# BRD1001-001-010-320_-_Clock.net
KiCad netlist of a schematic drawn in EAGLE
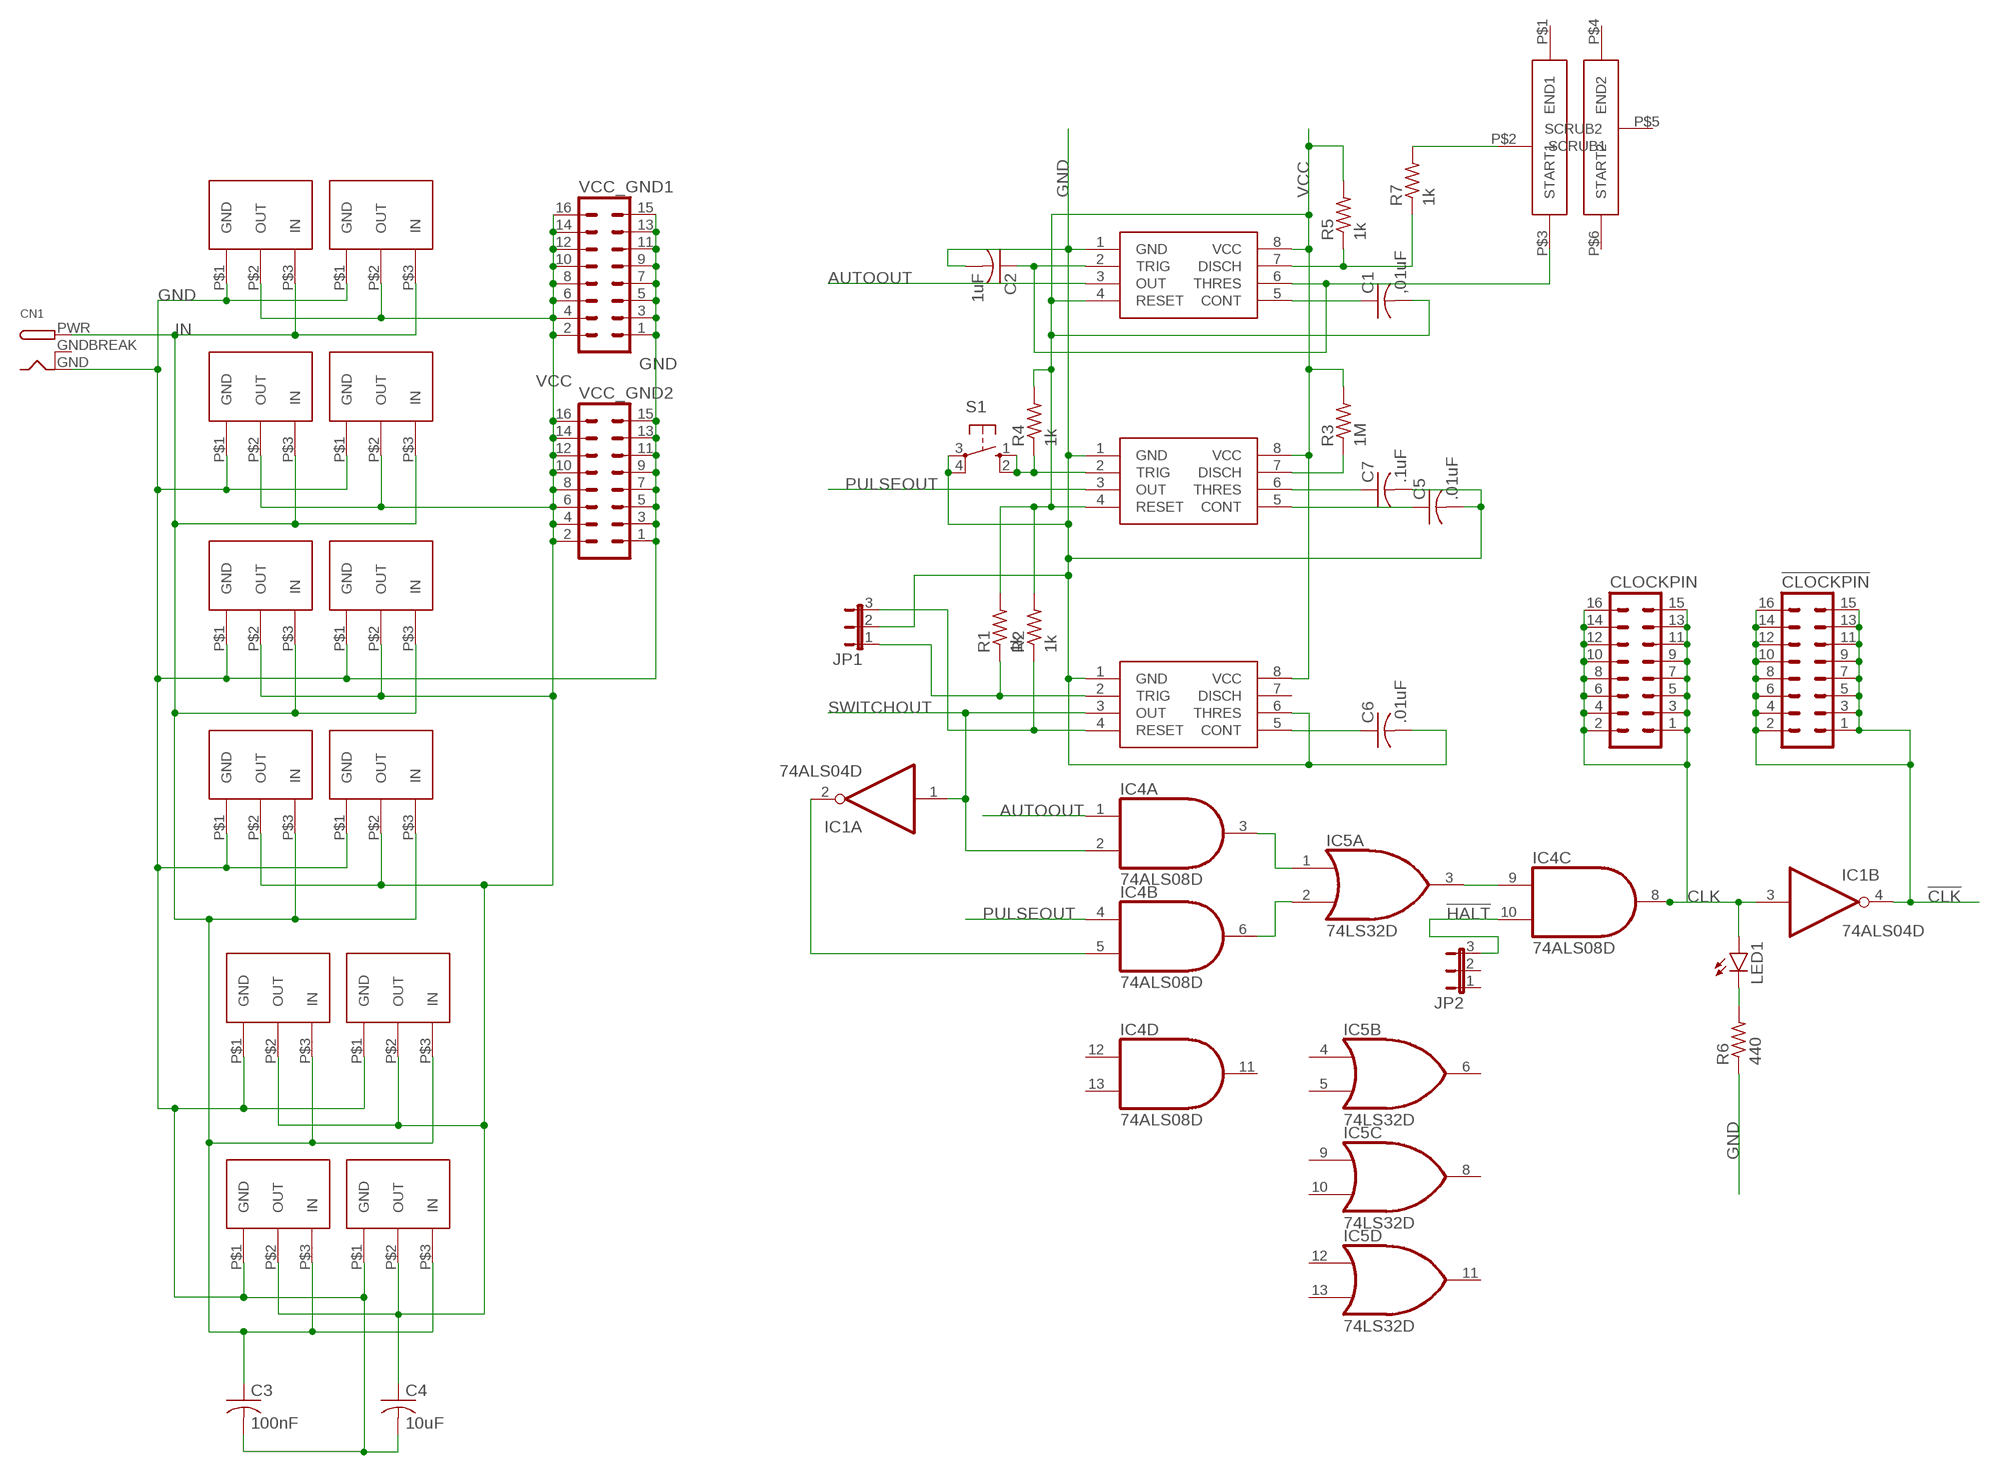
[diagram p0: schematic, sheet 1]

(export (version "E")
  (design (tool "Eeschema 10.0.6"))
  (components
    (comp (ref "!CLOCKPIN")
      (value "ML16")
      (footprint "eagle-import:ML16")
      (libsource (lib "eagle-import") (part "ML16"))
    )
    (comp (ref "AUTO")
      (value "NA555")
      (footprint "eagle-import:SO8")
      (libsource (lib "eagle-import") (part "NA555"))
    )
    (comp (ref "C1")
      (value ",01uF")
      (footprint "eagle-import:C025-024X044")
      (libsource (lib "eagle-import") (part "C-US025-024X044"))
    )
    (comp (ref "C2")
      (value "1uF")
      (footprint "eagle-import:C025-024X044")
      (libsource (lib "eagle-import") (part "C-US025-024X044"))
    )
    (comp (ref "C3")
      (value "100nF")
      (footprint "eagle-import:C025-024X044")
      (libsource (lib "eagle-import") (part "C-US025-024X044"))
    )
    (comp (ref "C4")
      (value "10uF")
      (footprint "eagle-import:C025-024X044")
      (libsource (lib "eagle-import") (part "C-US025-024X044"))
    )
    (comp (ref "C5")
      (value ".01uF")
      (footprint "eagle-import:C025-024X044")
      (libsource (lib "eagle-import") (part "C-US025-024X044"))
    )
    (comp (ref "C6")
      (value ".01uF")
      (footprint "eagle-import:C025-024X044")
      (libsource (lib "eagle-import") (part "C-US025-024X044"))
    )
    (comp (ref "C7")
      (value ".1uF")
      (footprint "eagle-import:C025-024X044")
      (libsource (lib "eagle-import") (part "C-US025-024X044"))
    )
    (comp (ref "CLOCKPIN")
      (value "ML16")
      (footprint "eagle-import:ML16")
      (libsource (lib "eagle-import") (part "ML16"))
    )
    (comp (ref "CN1")
      (value "DCBARRELPTH")
      (footprint "eagle-import:DCJACK_2MM_PTH")
      (libsource (lib "eagle-import") (part "DCBARRELPTH"))
    )
    (comp (ref "IC1")
      (value "74ALS04D")
      (footprint "eagle-import:SO14")
      (libsource (lib "eagle-import") (part "7404DALS"))
    )
    (comp (ref "IC4")
      (value "74ALS08D")
      (footprint "eagle-import:SO14")
      (libsource (lib "eagle-import") (part "7408DALS"))
    )
    (comp (ref "IC5")
      (value "74LS32D")
      (footprint "eagle-import:SO14")
      (libsource (lib "eagle-import") (part "7432DLS"))
    )
    (comp (ref "JP1")
      (value "JP2E")
      (footprint "eagle-import:JP2")
      (libsource (lib "eagle-import") (part "JP2E"))
    )
    (comp (ref "JP2")
      (value "JP2E")
      (footprint "eagle-import:JP2")
      (libsource (lib "eagle-import") (part "JP2E"))
    )
    (comp (ref "LED1")
      (value "LED5MM")
      (footprint "eagle-import:LED5MM")
      (libsource (lib "eagle-import") (part "LED5MM"))
    )
    (comp (ref "PULSE")
      (value "NA555")
      (footprint "eagle-import:SO8")
      (libsource (lib "eagle-import") (part "NA555"))
    )
    (comp (ref "R1")
      (value "1k")
      (footprint "eagle-import:0204V")
      (libsource (lib "eagle-import") (part "R-US_0204/2V"))
    )
    (comp (ref "R2")
      (value "1k")
      (footprint "eagle-import:0204V")
      (libsource (lib "eagle-import") (part "R-US_0204/2V"))
    )
    (comp (ref "R3")
      (value "1M")
      (footprint "eagle-import:0204V")
      (libsource (lib "eagle-import") (part "R-US_0204/2V"))
    )
    (comp (ref "R4")
      (value "1k")
      (footprint "eagle-import:0204V")
      (libsource (lib "eagle-import") (part "R-US_0204/2V"))
    )
    (comp (ref "R5")
      (value "1k")
      (footprint "eagle-import:0204V")
      (libsource (lib "eagle-import") (part "R-US_0204/2V"))
    )
    (comp (ref "R6")
      (value "440")
      (footprint "eagle-import:0204V")
      (libsource (lib "eagle-import") (part "R-US_0204/2V"))
    )
    (comp (ref "R7")
      (value "1k")
      (footprint "eagle-import:0204V")
      (libsource (lib "eagle-import") (part "R-US_0204/2V"))
    )
    (comp (ref "S1")
      (value "40-XX")
      (footprint "eagle-import:B3F-40XX")
      (fields (field (name "MF") "OMRON COMPONENTS USA") (field (name "MPN") "B3F-4000"))
      (libsource (lib "eagle-import") (part "40-XX"))
    )
    (comp (ref "SWITCH")
      (value "NA555")
      (footprint "eagle-import:SO8")
      (libsource (lib "eagle-import") (part "NA555"))
    )
    (comp (ref "U$1")
      (value "3310H-001-105L")
      (footprint "eagle-import:3310H-001-105L")
      (libsource (lib "eagle-import") (part "3310H-001-105L"))
    )
    (comp (ref "U$2")
      (value "LD1117S33TR")
      (footprint "eagle-import:AZ1117E")
      (libsource (lib "eagle-import") (part "LD1117S33TR"))
    )
    (comp (ref "U$3")
      (value "LD1117S33TR")
      (footprint "eagle-import:AZ1117E")
      (libsource (lib "eagle-import") (part "LD1117S33TR"))
    )
    (comp (ref "U$4")
      (value "LD1117S33TR")
      (footprint "eagle-import:AZ1117E")
      (libsource (lib "eagle-import") (part "LD1117S33TR"))
    )
    (comp (ref "U$5")
      (value "LD1117S33TR")
      (footprint "eagle-import:AZ1117E")
      (libsource (lib "eagle-import") (part "LD1117S33TR"))
    )
    (comp (ref "U$6")
      (value "LD1117S33TR")
      (footprint "eagle-import:AZ1117E")
      (libsource (lib "eagle-import") (part "LD1117S33TR"))
    )
    (comp (ref "U$7")
      (value "LD1117S33TR")
      (footprint "eagle-import:AZ1117E")
      (libsource (lib "eagle-import") (part "LD1117S33TR"))
    )
    (comp (ref "U$8")
      (value "LD1117S33TR")
      (footprint "eagle-import:AZ1117E")
      (libsource (lib "eagle-import") (part "LD1117S33TR"))
    )
    (comp (ref "U$9")
      (value "LD1117S33TR")
      (footprint "eagle-import:AZ1117E")
      (libsource (lib "eagle-import") (part "LD1117S33TR"))
    )
    (comp (ref "U$10")
      (value "LD1117S33TR")
      (footprint "eagle-import:AZ1117E")
      (libsource (lib "eagle-import") (part "LD1117S33TR"))
    )
    (comp (ref "U$11")
      (value "LD1117S33TR")
      (footprint "eagle-import:AZ1117E")
      (libsource (lib "eagle-import") (part "LD1117S33TR"))
    )
    (comp (ref "U$12")
      (value "LD1117S33TR")
      (footprint "eagle-import:AZ1117E")
      (libsource (lib "eagle-import") (part "LD1117S33TR"))
    )
    (comp (ref "U$13")
      (value "LD1117S33TR")
      (footprint "eagle-import:AZ1117E")
      (libsource (lib "eagle-import") (part "LD1117S33TR"))
    )
    (comp (ref "VCC_GND1")
      (value "ML16")
      (footprint "eagle-import:ML16")
      (libsource (lib "eagle-import") (part "ML16"))
    )
    (comp (ref "VCC_GND2")
      (value "ML16")
      (footprint "eagle-import:ML16")
      (libsource (lib "eagle-import") (part "ML16"))
    )
  )
  (nets
    (net (code "1") (name "/AUTOOUT") (class "Default")
      (node (ref "AUTO") (pin "3") (pinfunction "OUT_3") (pintype "bidirectional"))
      (node (ref "IC4") (pin "1") (pinfunction "I0_1") (pintype "input"))
    )
    (net (code "2") (name "/CLK") (class "Default")
      (node (ref "CLOCKPIN") (pin "1") (pinfunction "1_1") (pintype "passive"))
      (node (ref "CLOCKPIN") (pin "10") (pinfunction "10_10") (pintype "passive"))
      (node (ref "CLOCKPIN") (pin "11") (pinfunction "11_11") (pintype "passive"))
      (node (ref "CLOCKPIN") (pin "12") (pinfunction "12_12") (pintype "passive"))
      (node (ref "CLOCKPIN") (pin "13") (pinfunction "13_13") (pintype "passive"))
      (node (ref "CLOCKPIN") (pin "14") (pinfunction "14_14") (pintype "passive"))
      (node (ref "CLOCKPIN") (pin "15") (pinfunction "15_15") (pintype "passive"))
      (node (ref "CLOCKPIN") (pin "16") (pinfunction "16_16") (pintype "passive"))
      (node (ref "CLOCKPIN") (pin "2") (pinfunction "2_2") (pintype "passive"))
      (node (ref "CLOCKPIN") (pin "3") (pinfunction "3_3") (pintype "passive"))
      (node (ref "CLOCKPIN") (pin "4") (pinfunction "4_4") (pintype "passive"))
      (node (ref "CLOCKPIN") (pin "5") (pinfunction "5_5") (pintype "passive"))
      (node (ref "CLOCKPIN") (pin "6") (pinfunction "6_6") (pintype "passive"))
      (node (ref "CLOCKPIN") (pin "7") (pinfunction "7_7") (pintype "passive"))
      (node (ref "CLOCKPIN") (pin "8") (pinfunction "8_8") (pintype "passive"))
      (node (ref "CLOCKPIN") (pin "9") (pinfunction "9_9") (pintype "passive"))
      (node (ref "IC1") (pin "3") (pinfunction "I_3") (pintype "input"))
      (node (ref "IC4") (pin "8") (pinfunction "O_8") (pintype "output"))
      (node (ref "LED1") (pin "A") (pinfunction "A_A") (pintype "passive"))
    )
    (net (code "3") (name "/GND") (class "Default")
      (node (ref "AUTO") (pin "1") (pinfunction "GND_1") (pintype "bidirectional"))
      (node (ref "C2") (pin "2") (pinfunction "2_2") (pintype "passive"))
      (node (ref "C3") (pin "2") (pinfunction "2_2") (pintype "passive"))
      (node (ref "C4") (pin "2") (pinfunction "2_2") (pintype "passive"))
      (node (ref "C5") (pin "2") (pinfunction "2_2") (pintype "passive"))
      (node (ref "C6") (pin "2") (pinfunction "2_2") (pintype "passive"))
      (node (ref "C7") (pin "2") (pinfunction "2_2") (pintype "passive"))
      (node (ref "CN1") (pin "GND") (pinfunction "GND_GND") (pintype "power_in"))
      (node (ref "JP1") (pin "2") (pinfunction "2_2") (pintype "passive"))
      (node (ref "PULSE") (pin "1") (pinfunction "GND_1") (pintype "bidirectional"))
      (node (ref "R6") (pin "1") (pinfunction "1_1") (pintype "passive"))
      (node (ref "S1") (pin "3") (pinfunction "P_3") (pintype "passive"))
      (node (ref "S1") (pin "4") (pinfunction "P1_4") (pintype "passive"))
      (node (ref "SWITCH") (pin "1") (pinfunction "GND_1") (pintype "bidirectional"))
      (node (ref "SWITCH") (pin "6") (pinfunction "THRES_6") (pintype "bidirectional"))
      (node (ref "U$10") (pin "P$1") (pinfunction "GND_P$1") (pintype "bidirectional"))
      (node (ref "U$11") (pin "P$1") (pinfunction "GND_P$1") (pintype "bidirectional"))
      (node (ref "U$12") (pin "P$1") (pinfunction "GND_P$1") (pintype "bidirectional"))
      (node (ref "U$13") (pin "P$1") (pinfunction "GND_P$1") (pintype "bidirectional"))
      (node (ref "U$2") (pin "P$1") (pinfunction "GND_P$1") (pintype "bidirectional"))
      (node (ref "U$3") (pin "P$1") (pinfunction "GND_P$1") (pintype "bidirectional"))
      (node (ref "U$4") (pin "P$1") (pinfunction "GND_P$1") (pintype "bidirectional"))
      (node (ref "U$5") (pin "P$1") (pinfunction "GND_P$1") (pintype "bidirectional"))
      (node (ref "U$6") (pin "P$1") (pinfunction "GND_P$1") (pintype "bidirectional"))
      (node (ref "U$7") (pin "P$1") (pinfunction "GND_P$1") (pintype "bidirectional"))
      (node (ref "U$8") (pin "P$1") (pinfunction "GND_P$1") (pintype "bidirectional"))
      (node (ref "U$9") (pin "P$1") (pinfunction "GND_P$1") (pintype "bidirectional"))
      (node (ref "VCC_GND1") (pin "1") (pinfunction "1_1") (pintype "passive"))
      (node (ref "VCC_GND1") (pin "11") (pinfunction "11_11") (pintype "passive"))
      (node (ref "VCC_GND1") (pin "13") (pinfunction "13_13") (pintype "passive"))
      (node (ref "VCC_GND1") (pin "15") (pinfunction "15_15") (pintype "passive"))
      (node (ref "VCC_GND1") (pin "3") (pinfunction "3_3") (pintype "passive"))
      (node (ref "VCC_GND1") (pin "5") (pinfunction "5_5") (pintype "passive"))
      (node (ref "VCC_GND1") (pin "7") (pinfunction "7_7") (pintype "passive"))
      (node (ref "VCC_GND1") (pin "9") (pinfunction "9_9") (pintype "passive"))
      (node (ref "VCC_GND2") (pin "1") (pinfunction "1_1") (pintype "passive"))
      (node (ref "VCC_GND2") (pin "11") (pinfunction "11_11") (pintype "passive"))
      (node (ref "VCC_GND2") (pin "13") (pinfunction "13_13") (pintype "passive"))
      (node (ref "VCC_GND2") (pin "15") (pinfunction "15_15") (pintype "passive"))
      (node (ref "VCC_GND2") (pin "3") (pinfunction "3_3") (pintype "passive"))
      (node (ref "VCC_GND2") (pin "5") (pinfunction "5_5") (pintype "passive"))
      (node (ref "VCC_GND2") (pin "7") (pinfunction "7_7") (pintype "passive"))
      (node (ref "VCC_GND2") (pin "9") (pinfunction "9_9") (pintype "passive"))
    )
    (net (code "4") (name "/GNDBREAK") (class "Default")
      (node (ref "CN1") (pin "GNDBREAK") (pinfunction "GNDBREAK_GNDBREAK") (pintype "power_in"))
    )
    (net (code "5") (name "/IN") (class "Default")
      (node (ref "C3") (pin "1") (pinfunction "1_1") (pintype "passive"))
      (node (ref "CN1") (pin "PWR") (pinfunction "PWR_PWR") (pintype "power_in"))
      (node (ref "U$10") (pin "P$3") (pinfunction "IN_P$3") (pintype "bidirectional"))
      (node (ref "U$11") (pin "P$3") (pinfunction "IN_P$3") (pintype "bidirectional"))
      (node (ref "U$12") (pin "P$3") (pinfunction "IN_P$3") (pintype "bidirectional"))
      (node (ref "U$13") (pin "P$3") (pinfunction "IN_P$3") (pintype "bidirectional"))
      (node (ref "U$2") (pin "P$3") (pinfunction "IN_P$3") (pintype "bidirectional"))
      (node (ref "U$3") (pin "P$3") (pinfunction "IN_P$3") (pintype "bidirectional"))
      (node (ref "U$4") (pin "P$3") (pinfunction "IN_P$3") (pintype "bidirectional"))
      (node (ref "U$5") (pin "P$3") (pinfunction "IN_P$3") (pintype "bidirectional"))
      (node (ref "U$6") (pin "P$3") (pinfunction "IN_P$3") (pintype "bidirectional"))
      (node (ref "U$7") (pin "P$3") (pinfunction "IN_P$3") (pintype "bidirectional"))
      (node (ref "U$8") (pin "P$3") (pinfunction "IN_P$3") (pintype "bidirectional"))
      (node (ref "U$9") (pin "P$3") (pinfunction "IN_P$3") (pintype "bidirectional"))
    )
    (net (code "6") (name "/PULSEOUT") (class "Default")
      (node (ref "IC4") (pin "4") (pinfunction "I0_4") (pintype "input"))
      (node (ref "PULSE") (pin "3") (pinfunction "OUT_3") (pintype "bidirectional"))
    )
    (net (code "7") (name "/SWITCHOUT") (class "Default")
      (node (ref "IC1") (pin "1") (pinfunction "I_1") (pintype "input"))
      (node (ref "IC4") (pin "2") (pinfunction "I1_2") (pintype "input"))
      (node (ref "SWITCH") (pin "3") (pinfunction "OUT_3") (pintype "bidirectional"))
    )
    (net (code "8") (name "/VCC") (class "Default")
      (node (ref "AUTO") (pin "4") (pinfunction "RESET_4") (pintype "bidirectional"))
      (node (ref "AUTO") (pin "8") (pinfunction "VCC_8") (pintype "bidirectional"))
      (node (ref "C1") (pin "2") (pinfunction "2_2") (pintype "passive"))
      (node (ref "C4") (pin "1") (pinfunction "1_1") (pintype "passive"))
      (node (ref "PULSE") (pin "4") (pinfunction "RESET_4") (pintype "bidirectional"))
      (node (ref "PULSE") (pin "8") (pinfunction "VCC_8") (pintype "bidirectional"))
      (node (ref "R1") (pin "2") (pinfunction "2_2") (pintype "passive"))
      (node (ref "R2") (pin "2") (pinfunction "2_2") (pintype "passive"))
      (node (ref "R3") (pin "2") (pinfunction "2_2") (pintype "passive"))
      (node (ref "R4") (pin "2") (pinfunction "2_2") (pintype "passive"))
      (node (ref "R5") (pin "2") (pinfunction "2_2") (pintype "passive"))
      (node (ref "SWITCH") (pin "8") (pinfunction "VCC_8") (pintype "bidirectional"))
      (node (ref "U$10") (pin "P$2") (pinfunction "OUT_P$2") (pintype "bidirectional"))
      (node (ref "U$11") (pin "P$2") (pinfunction "OUT_P$2") (pintype "bidirectional"))
      (node (ref "U$12") (pin "P$2") (pinfunction "OUT_P$2") (pintype "bidirectional"))
      (node (ref "U$13") (pin "P$2") (pinfunction "OUT_P$2") (pintype "bidirectional"))
      (node (ref "U$2") (pin "P$2") (pinfunction "OUT_P$2") (pintype "bidirectional"))
      (node (ref "U$3") (pin "P$2") (pinfunction "OUT_P$2") (pintype "bidirectional"))
      (node (ref "U$4") (pin "P$2") (pinfunction "OUT_P$2") (pintype "bidirectional"))
      (node (ref "U$5") (pin "P$2") (pinfunction "OUT_P$2") (pintype "bidirectional"))
      (node (ref "U$6") (pin "P$2") (pinfunction "OUT_P$2") (pintype "bidirectional"))
      (node (ref "U$7") (pin "P$2") (pinfunction "OUT_P$2") (pintype "bidirectional"))
      (node (ref "U$8") (pin "P$2") (pinfunction "OUT_P$2") (pintype "bidirectional"))
      (node (ref "U$9") (pin "P$2") (pinfunction "OUT_P$2") (pintype "bidirectional"))
      (node (ref "VCC_GND1") (pin "10") (pinfunction "10_10") (pintype "passive"))
      (node (ref "VCC_GND1") (pin "12") (pinfunction "12_12") (pintype "passive"))
      (node (ref "VCC_GND1") (pin "14") (pinfunction "14_14") (pintype "passive"))
      (node (ref "VCC_GND1") (pin "16") (pinfunction "16_16") (pintype "passive"))
      (node (ref "VCC_GND1") (pin "2") (pinfunction "2_2") (pintype "passive"))
      (node (ref "VCC_GND1") (pin "4") (pinfunction "4_4") (pintype "passive"))
      (node (ref "VCC_GND1") (pin "6") (pinfunction "6_6") (pintype "passive"))
      (node (ref "VCC_GND1") (pin "8") (pinfunction "8_8") (pintype "passive"))
      (node (ref "VCC_GND2") (pin "10") (pinfunction "10_10") (pintype "passive"))
      (node (ref "VCC_GND2") (pin "12") (pinfunction "12_12") (pintype "passive"))
      (node (ref "VCC_GND2") (pin "14") (pinfunction "14_14") (pintype "passive"))
      (node (ref "VCC_GND2") (pin "16") (pinfunction "16_16") (pintype "passive"))
      (node (ref "VCC_GND2") (pin "2") (pinfunction "2_2") (pintype "passive"))
      (node (ref "VCC_GND2") (pin "4") (pinfunction "4_4") (pintype "passive"))
      (node (ref "VCC_GND2") (pin "6") (pinfunction "6_6") (pintype "passive"))
      (node (ref "VCC_GND2") (pin "8") (pinfunction "8_8") (pintype "passive"))
    )
    (net (code "9") (name "/~{CLK}") (class "Default")
      (node (ref "!CLOCKPIN") (pin "1") (pinfunction "1_1") (pintype "passive"))
      (node (ref "!CLOCKPIN") (pin "10") (pinfunction "10_10") (pintype "passive"))
      (node (ref "!CLOCKPIN") (pin "11") (pinfunction "11_11") (pintype "passive"))
      (node (ref "!CLOCKPIN") (pin "12") (pinfunction "12_12") (pintype "passive"))
      (node (ref "!CLOCKPIN") (pin "13") (pinfunction "13_13") (pintype "passive"))
      (node (ref "!CLOCKPIN") (pin "14") (pinfunction "14_14") (pintype "passive"))
      (node (ref "!CLOCKPIN") (pin "15") (pinfunction "15_15") (pintype "passive"))
      (node (ref "!CLOCKPIN") (pin "16") (pinfunction "16_16") (pintype "passive"))
      (node (ref "!CLOCKPIN") (pin "2") (pinfunction "2_2") (pintype "passive"))
      (node (ref "!CLOCKPIN") (pin "3") (pinfunction "3_3") (pintype "passive"))
      (node (ref "!CLOCKPIN") (pin "4") (pinfunction "4_4") (pintype "passive"))
      (node (ref "!CLOCKPIN") (pin "5") (pinfunction "5_5") (pintype "passive"))
      (node (ref "!CLOCKPIN") (pin "6") (pinfunction "6_6") (pintype "passive"))
      (node (ref "!CLOCKPIN") (pin "7") (pinfunction "7_7") (pintype "passive"))
      (node (ref "!CLOCKPIN") (pin "8") (pinfunction "8_8") (pintype "passive"))
      (node (ref "!CLOCKPIN") (pin "9") (pinfunction "9_9") (pintype "passive"))
      (node (ref "IC1") (pin "4") (pinfunction "O_4") (pintype "output"))
    )
    (net (code "10") (name "/~{HALT}") (class "Default")
      (node (ref "IC4") (pin "10") (pinfunction "I1_10") (pintype "input"))
      (node (ref "JP2") (pin "3") (pinfunction "3_3") (pintype "passive"))
    )
    (net (code "11") (name "Net-(AUTO-CONT)") (class "Default")
      (node (ref "AUTO") (pin "5") (pinfunction "CONT_5") (pintype "bidirectional"))
      (node (ref "C1") (pin "1") (pinfunction "1_1") (pintype "passive"))
    )
    (net (code "12") (name "Net-(AUTO-DISCH)") (class "Default")
      (node (ref "AUTO") (pin "7") (pinfunction "DISCH_7") (pintype "bidirectional"))
      (node (ref "R5") (pin "1") (pinfunction "1_1") (pintype "passive"))
      (node (ref "R7") (pin "1") (pinfunction "1_1") (pintype "passive"))
    )
    (net (code "13") (name "Net-(AUTO-THRES)") (class "Default")
      (node (ref "AUTO") (pin "2") (pinfunction "TRIG_2") (pintype "bidirectional"))
      (node (ref "AUTO") (pin "6") (pinfunction "THRES_6") (pintype "bidirectional"))
      (node (ref "C2") (pin "1") (pinfunction "1_1") (pintype "passive"))
      (node (ref "U$1") (pin "P$3") (pinfunction "START1_P$3") (pintype "bidirectional"))
    )
    (net (code "14") (name "Net-(IC1A-O)") (class "Default")
      (node (ref "IC1") (pin "2") (pinfunction "O_2") (pintype "output"))
      (node (ref "IC4") (pin "5") (pinfunction "I1_5") (pintype "input"))
    )
    (net (code "15") (name "Net-(IC4A-O)") (class "Default")
      (node (ref "IC4") (pin "3") (pinfunction "O_3") (pintype "output"))
      (node (ref "IC5") (pin "1") (pinfunction "I0_1") (pintype "input"))
    )
    (net (code "16") (name "Net-(IC4B-O)") (class "Default")
      (node (ref "IC4") (pin "6") (pinfunction "O_6") (pintype "output"))
      (node (ref "IC5") (pin "2") (pinfunction "I1_2") (pintype "input"))
    )
    (net (code "17") (name "Net-(IC4C-I0)") (class "Default")
      (node (ref "IC4") (pin "9") (pinfunction "I0_9") (pintype "input"))
      (node (ref "IC5") (pin "3") (pinfunction "O_3") (pintype "output"))
    )
    (net (code "18") (name "Net-(LED1-C)") (class "Default")
      (node (ref "LED1") (pin "K") (pinfunction "C_K") (pintype "passive"))
      (node (ref "R6") (pin "2") (pinfunction "2_2") (pintype "passive"))
    )
    (net (code "19") (name "Net-(PULSE-CONT)") (class "Default")
      (node (ref "C5") (pin "1") (pinfunction "1_1") (pintype "passive"))
      (node (ref "PULSE") (pin "5") (pinfunction "CONT_5") (pintype "bidirectional"))
    )
    (net (code "20") (name "Net-(PULSE-DISCH)") (class "Default")
      (node (ref "PULSE") (pin "7") (pinfunction "DISCH_7") (pintype "bidirectional"))
      (node (ref "R3") (pin "1") (pinfunction "1_1") (pintype "passive"))
    )
    (net (code "21") (name "Net-(PULSE-THRES)") (class "Default")
      (node (ref "C7") (pin "1") (pinfunction "1_1") (pintype "passive"))
      (node (ref "PULSE") (pin "6") (pinfunction "THRES_6") (pintype "bidirectional"))
    )
    (net (code "22") (name "Net-(PULSE-TRIG)") (class "Default")
      (node (ref "PULSE") (pin "2") (pinfunction "TRIG_2") (pintype "bidirectional"))
      (node (ref "R4") (pin "1") (pinfunction "1_1") (pintype "passive"))
      (node (ref "S1") (pin "1") (pinfunction "S_1") (pintype "passive"))
      (node (ref "S1") (pin "2") (pinfunction "S1_2") (pintype "passive"))
    )
    (net (code "23") (name "Net-(SWITCH-CONT)") (class "Default")
      (node (ref "C6") (pin "1") (pinfunction "1_1") (pintype "passive"))
      (node (ref "SWITCH") (pin "5") (pinfunction "CONT_5") (pintype "bidirectional"))
    )
    (net (code "24") (name "Net-(SWITCH-RESET)") (class "Default")
      (node (ref "JP1") (pin "3") (pinfunction "3_3") (pintype "passive"))
      (node (ref "R2") (pin "1") (pinfunction "1_1") (pintype "passive"))
      (node (ref "SWITCH") (pin "4") (pinfunction "RESET_4") (pintype "bidirectional"))
    )
    (net (code "25") (name "Net-(SWITCH-TRIG)") (class "Default")
      (node (ref "JP1") (pin "1") (pinfunction "1_1") (pintype "passive"))
      (node (ref "R1") (pin "1") (pinfunction "1_1") (pintype "passive"))
      (node (ref "SWITCH") (pin "2") (pinfunction "TRIG_2") (pintype "bidirectional"))
    )
    (net (code "26") (name "Net-(U$1-SCRUB1)") (class "Default")
      (node (ref "R7") (pin "2") (pinfunction "2_2") (pintype "passive"))
      (node (ref "U$1") (pin "P$2") (pinfunction "SCRUB1_P$2") (pintype "bidirectional"))
    )
    (net (code "27") (name "unconnected-(IC4D-I0-Pad12)") (class "Default")
      (node (ref "IC4") (pin "12") (pinfunction "I0_12") (pintype "input"))
    )
    (net (code "28") (name "unconnected-(IC4D-I1-Pad13)") (class "Default")
      (node (ref "IC4") (pin "13") (pinfunction "I1_13") (pintype "input"))
    )
    (net (code "29") (name "unconnected-(IC4D-O-Pad11)") (class "Default")
      (node (ref "IC4") (pin "11") (pinfunction "O_11") (pintype "output"))
    )
    (net (code "30") (name "unconnected-(IC5B-I0-Pad4)") (class "Default")
      (node (ref "IC5") (pin "4") (pinfunction "I0_4") (pintype "input"))
    )
    (net (code "31") (name "unconnected-(IC5B-I1-Pad5)") (class "Default")
      (node (ref "IC5") (pin "5") (pinfunction "I1_5") (pintype "input"))
    )
    (net (code "32") (name "unconnected-(IC5B-O-Pad6)") (class "Default")
      (node (ref "IC5") (pin "6") (pinfunction "O_6") (pintype "output"))
    )
    (net (code "33") (name "unconnected-(IC5C-I0-Pad9)") (class "Default")
      (node (ref "IC5") (pin "9") (pinfunction "I0_9") (pintype "input"))
    )
    (net (code "34") (name "unconnected-(IC5C-I1-Pad10)") (class "Default")
      (node (ref "IC5") (pin "10") (pinfunction "I1_10") (pintype "input"))
    )
    (net (code "35") (name "unconnected-(IC5C-O-Pad8)") (class "Default")
      (node (ref "IC5") (pin "8") (pinfunction "O_8") (pintype "output"))
    )
    (net (code "36") (name "unconnected-(IC5D-I0-Pad12)") (class "Default")
      (node (ref "IC5") (pin "12") (pinfunction "I0_12") (pintype "input"))
    )
    (net (code "37") (name "unconnected-(IC5D-I1-Pad13)") (class "Default")
      (node (ref "IC5") (pin "13") (pinfunction "I1_13") (pintype "input"))
    )
    (net (code "38") (name "unconnected-(IC5D-O-Pad11)") (class "Default")
      (node (ref "IC5") (pin "11") (pinfunction "O_11") (pintype "output"))
    )
    (net (code "39") (name "unconnected-(JP2-Pad1)") (class "Default")
      (node (ref "JP2") (pin "1") (pinfunction "1_1") (pintype "passive"))
    )
    (net (code "40") (name "unconnected-(JP2-Pad2)") (class "Default")
      (node (ref "JP2") (pin "2") (pinfunction "2_2") (pintype "passive"))
    )
    (net (code "41") (name "unconnected-(SWITCH-DISCH-Pad7)") (class "Default")
      (node (ref "SWITCH") (pin "7") (pinfunction "DISCH_7") (pintype "bidirectional"))
    )
    (net (code "42") (name "unconnected-(U$1-END1-PadP$1)") (class "Default")
      (node (ref "U$1") (pin "P$1") (pinfunction "END1_P$1") (pintype "bidirectional"))
    )
    (net (code "43") (name "unconnected-(U$1-END2-PadP$4)") (class "Default")
      (node (ref "U$1") (pin "P$4") (pinfunction "END2_P$4") (pintype "bidirectional"))
    )
    (net (code "44") (name "unconnected-(U$1-SCRUB2-PadP$5)") (class "Default")
      (node (ref "U$1") (pin "P$5") (pinfunction "SCRUB2_P$5") (pintype "bidirectional"))
    )
    (net (code "45") (name "unconnected-(U$1-START2-PadP$6)") (class "Default")
      (node (ref "U$1") (pin "P$6") (pinfunction "START2_P$6") (pintype "bidirectional"))
    )
  )
)
